# Power_Supply.net
KiCad netlist of a schematic drawn in Altium Designer
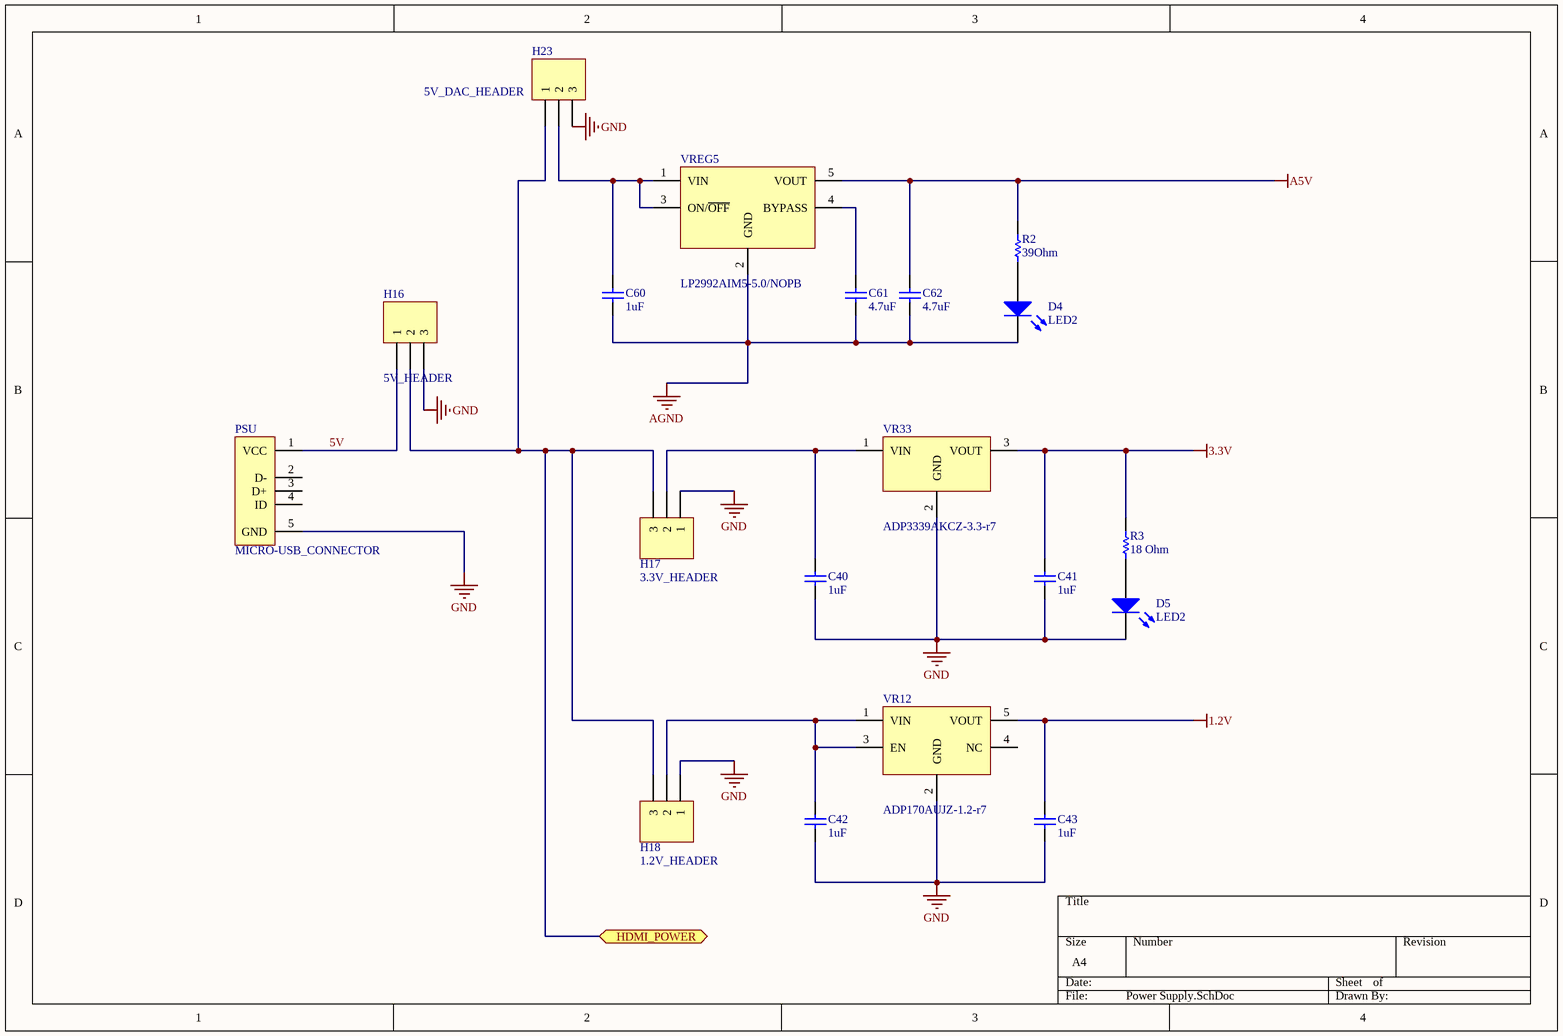
[diagram p0: Power Supply.SchDoc]

(export (version "E")
  (design (tool "Eeschema 10.0.6"))
  (components
    (comp (ref "C40")
      (value "1uF")
      (footprint "CAPC0603(1608)100_M")
      (description "CAP 0.5pF 10V Â±0.1pF 0603 (1608 Metric) Thickness 1mm SMD")
      (fields (field (name "TOLERANCE") "Â±0.1pF"))
      (libsource (lib "Altium Inc") (part "CMP-1035-00001-1"))
    )
    (comp (ref "C41")
      (value "1uF")
      (footprint "CAPC0603(1608)100_M")
      (description "CAP 0.5pF 10V Â±0.1pF 0603 (1608 Metric) Thickness 1mm SMD")
      (fields (field (name "TOLERANCE") "Â±0.1pF"))
      (libsource (lib "Altium Inc") (part "CMP-1035-00001-1"))
    )
    (comp (ref "C42")
      (value "1uF")
      (footprint "CAPC0603(1608)100_M")
      (description "CAP 0.5pF 10V Â±0.1pF 0603 (1608 Metric) Thickness 1mm SMD")
      (fields (field (name "TOLERANCE") "Â±0.1pF"))
      (libsource (lib "Altium Inc") (part "CMP-1035-00001-1"))
    )
    (comp (ref "C43")
      (value "1uF")
      (footprint "CAPC0603(1608)100_M")
      (description "CAP 0.5pF 10V Â±0.1pF 0603 (1608 Metric) Thickness 1mm SMD")
      (fields (field (name "TOLERANCE") "Â±0.1pF"))
      (libsource (lib "Altium Inc") (part "CMP-1035-00001-1"))
    )
    (comp (ref "C60")
      (value "1uF")
      (footprint "CAPC0603(1608)100_M")
      (description "CAP 0.5pF 10V Â±0.1pF 0603 (1608 Metric) Thickness 1mm SMD")
      (fields (field (name "TOLERANCE") "Â±0.1pF"))
      (libsource (lib "Altium Inc") (part "CMP-1035-00001-1"))
    )
    (comp (ref "C61")
      (value "4.7uF")
      (footprint "CAPC0603(1608)100_M")
      (description "CAP 0.5pF 10V Â±0.1pF 0603 (1608 Metric) Thickness 1mm SMD")
      (fields (field (name "TOLERANCE") "Â±0.1pF"))
      (libsource (lib "Altium Inc") (part "CMP-1035-00001-1"))
    )
    (comp (ref "C62")
      (value "4.7uF")
      (footprint "CAPC0603(1608)100_M")
      (description "CAP 0.5pF 10V Â±0.1pF 0603 (1608 Metric) Thickness 1mm SMD")
      (fields (field (name "TOLERANCE") "Â±0.1pF"))
      (libsource (lib "Altium Inc") (part "CMP-1035-00001-1"))
    )
    (comp (ref "D4")
      (value "LED2")
      (footprint "3.2X1.6X1.1")
      (description "Typical RED, GREEN, YELLOW, AMBER GaAs LED")
      (fields (field (name "PUBLISHER") "Altium Limited"))
      (libsource (lib "Miscellaneous Devices") (part "LED2"))
    )
    (comp (ref "D5")
      (value "LED2")
      (footprint "3.2X1.6X1.1")
      (description "Typical RED, GREEN, YELLOW, AMBER GaAs LED")
      (fields (field (name "PUBLISHER") "Altium Limited"))
      (libsource (lib "Miscellaneous Devices") (part "LED2"))
    )
    (comp (ref "H16")
      (value "5V_HEADER")
      (footprint "HDR1X3")
      (description "Header, 3-Pin")
      (fields (field (name "PUBLISHER") "Altium Limited"))
      (libsource (lib "") (part "Header 3_1"))
    )
    (comp (ref "H17")
      (value "3.3V_HEADER")
      (footprint "HDR1X3")
      (description "Header, 3-Pin")
      (fields (field (name "PUBLISHER") "Altium Limited"))
      (libsource (lib "Miscellaneous Connectors") (part "Header 3"))
    )
    (comp (ref "H18")
      (value "1.2V_HEADER")
      (footprint "HDR1X3")
      (description "Header, 3-Pin")
      (fields (field (name "PUBLISHER") "Altium Limited"))
      (libsource (lib "Miscellaneous Connectors") (part "Header 3"))
    )
    (comp (ref "H23")
      (value "5V_DAC_HEADER")
      (footprint "HDR1X3")
      (description "Header, 3-Pin")
      (fields (field (name "PUBLISHER") "Altium Limited"))
      (libsource (lib "") (part "Header 3_1"))
    )
    (comp (ref "PSU")
      (value "MICRO-USB_CONNECTOR")
      (footprint "MICRO-USB")
      (libsource (lib "Vector Library") (part "MICRO-USB_CONNECTOR"))
    )
    (comp (ref "R2")
      (value "39Ohm")
      (footprint "RESC0603(1608)_M")
      (description "1R 0.1W 5% 0603 (1608 Metric)  SMD")
      (fields (field (name "POWER") "0.1 W") (field (name "TOLERANCE") "5 %"))
      (libsource (lib "Altium Inc") (part "CMP-1012-00002-1"))
    )
    (comp (ref "R3")
      (value "18 Ohm")
      (footprint "RESC0603(1608)_M")
      (description "1R 0.1W 5% 0603 (1608 Metric)  SMD")
      (fields (field (name "POWER") "0.1 W") (field (name "TOLERANCE") "5 %"))
      (libsource (lib "Altium Inc") (part "CMP-1012-00002-1"))
    )
    (comp (ref "VR12")
      (value "ADP170AUJZ-1.2-r7")
      (footprint "VREG-1.2")
      (libsource (lib "Vector Library") (part "ADP170AUJZ-1.2-r7"))
    )
    (comp (ref "VR33")
      (value "ADP3339AKCZ-3.3-r7")
      (footprint "VREG-3.3")
      (libsource (lib "Vector Library") (part "ADP3339AKCZ-3.3-r7"))
    )
    (comp (ref "VREG5")
      (value "LP2992AIM5-5.0/NOPB")
      (footprint "VREG-5")
      (libsource (lib "Vector Library") (part "LP2992AIM5-5.0/NOPB"))
    )
  )
  (nets
    (net (code "1") (name "/5V") (class "Default")
      (node (ref "H16") (pin "1") (pinfunction "1_1") (pintype "passive"))
      (node (ref "PSU") (pin "1") (pinfunction "VCC_1") (pintype "passive"))
    )
    (net (code "2") (name "/HDMI_POWER") (class "Default")
      (node (ref "H16") (pin "2") (pinfunction "2_2") (pintype "passive"))
      (node (ref "H17") (pin "3") (pinfunction "3_3") (pintype "passive"))
      (node (ref "H18") (pin "3") (pinfunction "3_3") (pintype "passive"))
      (node (ref "H23") (pin "1") (pinfunction "1_1") (pintype "passive"))
    )
    (net (code "3") (name "1.2V") (class "Default")
      (node (ref "C43") (pin "2") (pinfunction "2_2") (pintype "passive"))
      (node (ref "VR12") (pin "5") (pinfunction "VOUT_5") (pintype "passive"))
    )
    (net (code "4") (name "3.3V") (class "Default")
      (node (ref "C41") (pin "2") (pinfunction "2_2") (pintype "passive"))
      (node (ref "R3") (pin "2") (pinfunction "2_2") (pintype "passive"))
      (node (ref "VR33") (pin "3") (pinfunction "VOUT_3") (pintype "passive"))
    )
    (net (code "5") (name "A5V") (class "Default")
      (node (ref "C62") (pin "2") (pinfunction "2_2") (pintype "passive"))
      (node (ref "R2") (pin "2") (pinfunction "2_2") (pintype "passive"))
      (node (ref "VREG5") (pin "5") (pinfunction "VOUT_5") (pintype "passive"))
    )
    (net (code "6") (name "AGND") (class "Default")
      (node (ref "C60") (pin "1") (pinfunction "1_1") (pintype "passive"))
      (node (ref "C61") (pin "1") (pinfunction "1_1") (pintype "passive"))
      (node (ref "C62") (pin "1") (pinfunction "1_1") (pintype "passive"))
      (node (ref "D4") (pin "2") (pinfunction "K_2") (pintype "passive"))
      (node (ref "VREG5") (pin "2") (pinfunction "GND_2") (pintype "passive"))
    )
    (net (code "7") (name "GND") (class "Default")
      (node (ref "C40") (pin "1") (pinfunction "1_1") (pintype "passive"))
      (node (ref "C41") (pin "1") (pinfunction "1_1") (pintype "passive"))
      (node (ref "C42") (pin "1") (pinfunction "1_1") (pintype "passive"))
      (node (ref "C43") (pin "1") (pinfunction "1_1") (pintype "passive"))
      (node (ref "D5") (pin "2") (pinfunction "K_2") (pintype "passive"))
      (node (ref "H16") (pin "3") (pinfunction "3_3") (pintype "passive"))
      (node (ref "H17") (pin "1") (pinfunction "1_1") (pintype "passive"))
      (node (ref "H18") (pin "1") (pinfunction "1_1") (pintype "passive"))
      (node (ref "H23") (pin "3") (pinfunction "3_3") (pintype "passive"))
      (node (ref "PSU") (pin "5") (pinfunction "GND_5") (pintype "passive"))
      (node (ref "VR12") (pin "2") (pinfunction "GND_2") (pintype "passive"))
      (node (ref "VR33") (pin "2") (pinfunction "GND_2") (pintype "passive"))
    )
    (net (code "8") (name "Net-(D4-A)") (class "Default")
      (node (ref "D4") (pin "1") (pinfunction "A_1") (pintype "passive"))
      (node (ref "R2") (pin "1") (pinfunction "1_1") (pintype "passive"))
    )
    (net (code "9") (name "Net-(D5-A)") (class "Default")
      (node (ref "D5") (pin "1") (pinfunction "A_1") (pintype "passive"))
      (node (ref "R3") (pin "1") (pinfunction "1_1") (pintype "passive"))
    )
    (net (code "10") (name "Net-(VR12-EN)") (class "Default")
      (node (ref "C42") (pin "2") (pinfunction "2_2") (pintype "passive"))
      (node (ref "H18") (pin "2") (pinfunction "2_2") (pintype "passive"))
      (node (ref "VR12") (pin "1") (pinfunction "VIN_1") (pintype "passive"))
      (node (ref "VR12") (pin "3") (pinfunction "EN_3") (pintype "passive"))
    )
    (net (code "11") (name "Net-(VR33-VIN)") (class "Default")
      (node (ref "C40") (pin "2") (pinfunction "2_2") (pintype "passive"))
      (node (ref "H17") (pin "2") (pinfunction "2_2") (pintype "passive"))
      (node (ref "VR33") (pin "1") (pinfunction "VIN_1") (pintype "passive"))
    )
    (net (code "12") (name "Net-(VREG5-BYPASS)") (class "Default")
      (node (ref "C61") (pin "2") (pinfunction "2_2") (pintype "passive"))
      (node (ref "VREG5") (pin "4") (pinfunction "BYPASS_4") (pintype "passive"))
    )
    (net (code "13") (name "Net-(VREG5-ON{slash}~{OFF})") (class "Default")
      (node (ref "C60") (pin "2") (pinfunction "2_2") (pintype "passive"))
      (node (ref "H23") (pin "2") (pinfunction "2_2") (pintype "passive"))
      (node (ref "VREG5") (pin "1") (pinfunction "VIN_1") (pintype "passive"))
      (node (ref "VREG5") (pin "3") (pinfunction "ON/~{OFF}_3") (pintype "passive"))
    )
    (net (code "14") (name "unconnected-(PSU-D+-Pad3)") (class "Default")
      (node (ref "PSU") (pin "3") (pinfunction "D+_3") (pintype "passive"))
    )
    (net (code "15") (name "unconnected-(PSU-D--Pad2)") (class "Default")
      (node (ref "PSU") (pin "2") (pinfunction "D-_2") (pintype "passive"))
    )
    (net (code "16") (name "unconnected-(PSU-ID-Pad4)") (class "Default")
      (node (ref "PSU") (pin "4") (pinfunction "ID_4") (pintype "passive"))
    )
    (net (code "17") (name "unconnected-(VR12-NC-Pad4)") (class "Default")
      (node (ref "VR12") (pin "4") (pinfunction "NC_4") (pintype "passive"))
    )
  )
)
